# 3_TB6612_2_schdoc.net
KiCad netlist of a schematic drawn in Altium Designer
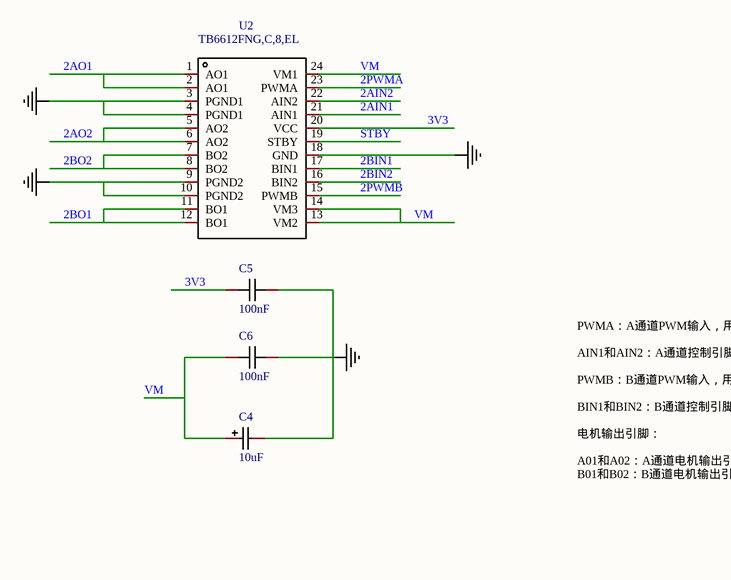
[diagram p0: 3_TB6612（2）.schdoc.schdoc]

(export (version "E")
  (design (tool "Eeschema 10.0.6"))
  (components
    (comp (ref "C4")
      (value "10uF")
      (fields
        (field (name "NAME") "10uF")
        (field (name "MANUFACTURER") "Kyocera AVX")
        (field (name "MANUFACTURER PART") "TAJB106K025RNJ")
        (field (name "TOLERANCE") "±10%")
      )
      (libsource (lib "altium-import") (part "root_2_TAJB106K025RNJ_"))
    )
    (comp (ref "C5")
      (value "100nF")
      (fields (field (name "NAME") "100nF"))
      (libsource (lib "altium-import") (part "root_0_CAP_0603_"))
    )
    (comp (ref "C6")
      (value "100nF")
      (fields (field (name "NAME") "100nF"))
      (libsource (lib "altium-import") (part "root_0_CAP_0603_"))
    )
    (comp (ref "U2")
      (value "TB6612FNG,C,8,EL")
      (description "驱动电机类型:有刷直流电机;电源电压:2.7V~5.5V;输出电流:1A;接口:并行;")
      (fields (field (name "NAME") "TB6612FNG,C,8,EL") (field (name "MANUFACTURER") "TOSHIBA(东芝)"))
      (libsource (lib "altium-import") (part "root_0_TB6612FNG,C,8,EL_"))
    )
  )
  (nets
    (net (code "1") (name "/2AIN1") (class "Default")
      (node (ref "U2") (pin "21") (pinfunction "AIN1_21") (pintype "passive"))
    )
    (net (code "2") (name "/2AIN2") (class "Default")
      (node (ref "U2") (pin "22") (pinfunction "AIN2_22") (pintype "passive"))
    )
    (net (code "3") (name "/2AO1") (class "Default")
      (node (ref "U2") (pin "1") (pinfunction "AO1_1") (pintype "passive"))
      (node (ref "U2") (pin "2") (pinfunction "AO1_2") (pintype "passive"))
    )
    (net (code "4") (name "/2AO2") (class "Default")
      (node (ref "U2") (pin "5") (pinfunction "AO2_5") (pintype "passive"))
      (node (ref "U2") (pin "6") (pinfunction "AO2_6") (pintype "passive"))
    )
    (net (code "5") (name "/2BIN1") (class "Default")
      (node (ref "U2") (pin "17") (pinfunction "BIN1_17") (pintype "passive"))
    )
    (net (code "6") (name "/2BIN2") (class "Default")
      (node (ref "U2") (pin "16") (pinfunction "BIN2_16") (pintype "passive"))
    )
    (net (code "7") (name "/2BO1") (class "Default")
      (node (ref "U2") (pin "11") (pinfunction "BO1_11") (pintype "passive"))
      (node (ref "U2") (pin "12") (pinfunction "BO1_12") (pintype "passive"))
    )
    (net (code "8") (name "/2BO2") (class "Default")
      (node (ref "U2") (pin "7") (pinfunction "BO2_7") (pintype "passive"))
      (node (ref "U2") (pin "8") (pinfunction "BO2_8") (pintype "passive"))
    )
    (net (code "9") (name "/2PWMA") (class "Default")
      (node (ref "U2") (pin "23") (pinfunction "PWMA_23") (pintype "passive"))
    )
    (net (code "10") (name "/2PWMB") (class "Default")
      (node (ref "U2") (pin "15") (pinfunction "PWMB_15") (pintype "passive"))
    )
    (net (code "11") (name "/3V3") (class "Default")
      (node (ref "C5") (pin "1") (pinfunction "1_1") (pintype "passive"))
      (node (ref "U2") (pin "20") (pinfunction "VCC_20") (pintype "passive"))
    )
    (net (code "12") (name "/STBY") (class "Default")
      (node (ref "U2") (pin "19") (pinfunction "STBY_19") (pintype "passive"))
    )
    (net (code "13") (name "/VM") (class "Default")
      (node (ref "C4") (pin "1") (pinfunction "1_1") (pintype "passive"))
      (node (ref "C6") (pin "1") (pinfunction "1_1") (pintype "passive"))
      (node (ref "U2") (pin "13") (pinfunction "VM2_13") (pintype "passive"))
      (node (ref "U2") (pin "14") (pinfunction "VM3_14") (pintype "passive"))
      (node (ref "U2") (pin "24") (pinfunction "VM1_24") (pintype "passive"))
    )
    (net (code "14") (name "<NO NET>") (class "Default")
      (node (ref "C4") (pin "2") (pinfunction "2_2") (pintype "passive"))
      (node (ref "C5") (pin "2") (pinfunction "2_2") (pintype "passive"))
      (node (ref "C6") (pin "2") (pinfunction "2_2") (pintype "passive"))
      (node (ref "U2") (pin "10") (pinfunction "PGND2_10") (pintype "passive"))
      (node (ref "U2") (pin "18") (pinfunction "GND_18") (pintype "passive"))
      (node (ref "U2") (pin "3") (pinfunction "PGND1_3") (pintype "passive"))
      (node (ref "U2") (pin "4") (pinfunction "PGND1_4") (pintype "passive"))
      (node (ref "U2") (pin "9") (pinfunction "PGND2_9") (pintype "passive"))
    )
  )
)
